# MicroController_Module_Output_Ports.net
KiCad netlist of a schematic drawn in Altium Designer
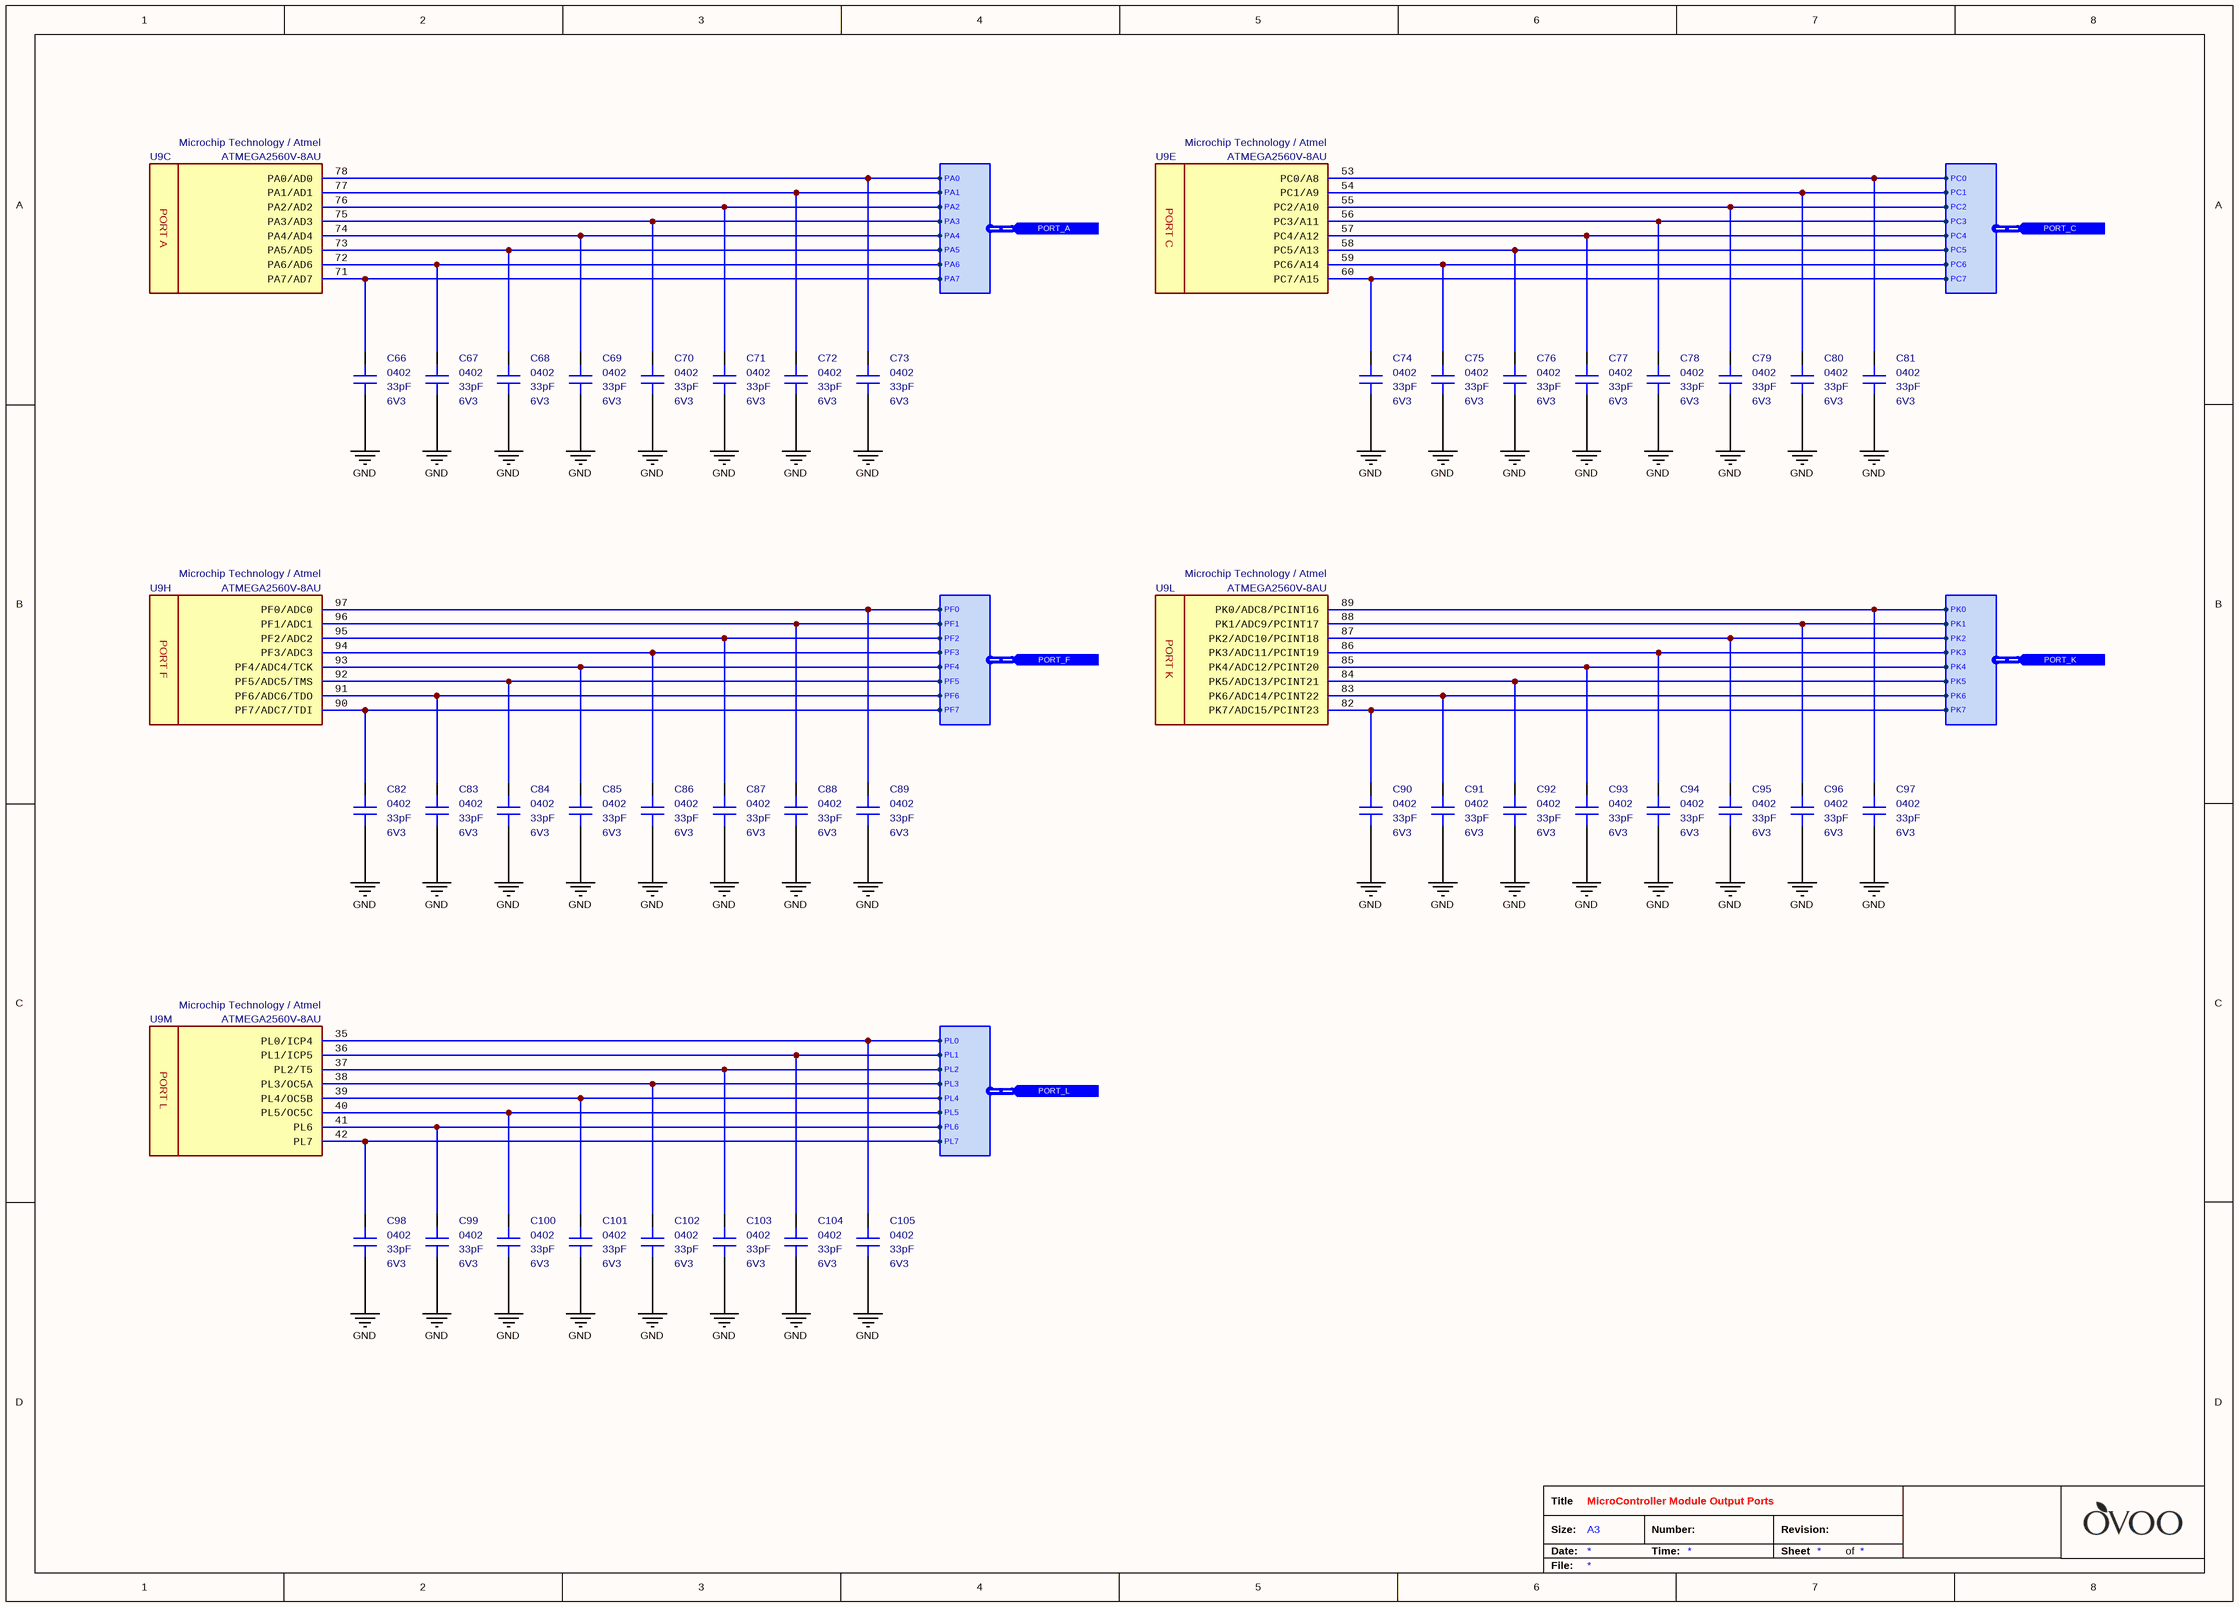
[diagram p0: MicroController Module Output Ports.SchDoc]

(export (version "E")
  (design (tool "Eeschema 10.0.6"))
  (components
    (comp (ref "C66")
      (value "33pF")
      (footprint "CAPACITOR_0402")
      (description "Capacitor - 33pF [0402] (Ceramic)")
      (fields
        (field (name "MANUFACTURER_PART_NUMBER") "C0402C330J9RACAUTO")
        (field (name "MOUSER_PART_NUMBER") "80-C0402C330J9RAUTO")
        (field (name "CASE") "0402")
        (field (name "VOLTAGE") "6V3")
      )
      (libsource (lib "Ovoo_Schematic") (part "Capacitor - 33pF [0402-6V3]"))
    )
    (comp (ref "C67")
      (value "33pF")
      (footprint "CAPACITOR_0402")
      (description "Capacitor - 33pF [0402] (Ceramic)")
      (fields
        (field (name "MANUFACTURER_PART_NUMBER") "C0402C330J9RACAUTO")
        (field (name "MOUSER_PART_NUMBER") "80-C0402C330J9RAUTO")
        (field (name "CASE") "0402")
        (field (name "VOLTAGE") "6V3")
      )
      (libsource (lib "Ovoo_Schematic") (part "Capacitor - 33pF [0402-6V3]"))
    )
    (comp (ref "C68")
      (value "33pF")
      (footprint "CAPACITOR_0402")
      (description "Capacitor - 33pF [0402] (Ceramic)")
      (fields
        (field (name "MANUFACTURER_PART_NUMBER") "C0402C330J9RACAUTO")
        (field (name "MOUSER_PART_NUMBER") "80-C0402C330J9RAUTO")
        (field (name "CASE") "0402")
        (field (name "VOLTAGE") "6V3")
      )
      (libsource (lib "Ovoo_Schematic") (part "Capacitor - 33pF [0402-6V3]"))
    )
    (comp (ref "C69")
      (value "33pF")
      (footprint "CAPACITOR_0402")
      (description "Capacitor - 33pF [0402] (Ceramic)")
      (fields
        (field (name "MANUFACTURER_PART_NUMBER") "C0402C330J9RACAUTO")
        (field (name "MOUSER_PART_NUMBER") "80-C0402C330J9RAUTO")
        (field (name "CASE") "0402")
        (field (name "VOLTAGE") "6V3")
      )
      (libsource (lib "Ovoo_Schematic") (part "Capacitor - 33pF [0402-6V3]"))
    )
    (comp (ref "C70")
      (value "33pF")
      (footprint "CAPACITOR_0402")
      (description "Capacitor - 33pF [0402] (Ceramic)")
      (fields
        (field (name "MANUFACTURER_PART_NUMBER") "C0402C330J9RACAUTO")
        (field (name "MOUSER_PART_NUMBER") "80-C0402C330J9RAUTO")
        (field (name "CASE") "0402")
        (field (name "VOLTAGE") "6V3")
      )
      (libsource (lib "Ovoo_Schematic") (part "Capacitor - 33pF [0402-6V3]"))
    )
    (comp (ref "C71")
      (value "33pF")
      (footprint "CAPACITOR_0402")
      (description "Capacitor - 33pF [0402] (Ceramic)")
      (fields
        (field (name "MANUFACTURER_PART_NUMBER") "C0402C330J9RACAUTO")
        (field (name "MOUSER_PART_NUMBER") "80-C0402C330J9RAUTO")
        (field (name "CASE") "0402")
        (field (name "VOLTAGE") "6V3")
      )
      (libsource (lib "Ovoo_Schematic") (part "Capacitor - 33pF [0402-6V3]"))
    )
    (comp (ref "C72")
      (value "33pF")
      (footprint "CAPACITOR_0402")
      (description "Capacitor - 33pF [0402] (Ceramic)")
      (fields
        (field (name "MANUFACTURER_PART_NUMBER") "C0402C330J9RACAUTO")
        (field (name "MOUSER_PART_NUMBER") "80-C0402C330J9RAUTO")
        (field (name "CASE") "0402")
        (field (name "VOLTAGE") "6V3")
      )
      (libsource (lib "Ovoo_Schematic") (part "Capacitor - 33pF [0402-6V3]"))
    )
    (comp (ref "C73")
      (value "33pF")
      (footprint "CAPACITOR_0402")
      (description "Capacitor - 33pF [0402] (Ceramic)")
      (fields
        (field (name "MANUFACTURER_PART_NUMBER") "C0402C330J9RACAUTO")
        (field (name "MOUSER_PART_NUMBER") "80-C0402C330J9RAUTO")
        (field (name "CASE") "0402")
        (field (name "VOLTAGE") "6V3")
      )
      (libsource (lib "Ovoo_Schematic") (part "Capacitor - 33pF [0402-6V3]"))
    )
    (comp (ref "C74")
      (value "33pF")
      (footprint "CAPACITOR_0402")
      (description "Capacitor - 33pF [0402] (Ceramic)")
      (fields
        (field (name "MANUFACTURER_PART_NUMBER") "C0402C330J9RACAUTO")
        (field (name "MOUSER_PART_NUMBER") "80-C0402C330J9RAUTO")
        (field (name "CASE") "0402")
        (field (name "VOLTAGE") "6V3")
      )
      (libsource (lib "Ovoo_Schematic") (part "Capacitor - 33pF [0402-6V3]"))
    )
    (comp (ref "C75")
      (value "33pF")
      (footprint "CAPACITOR_0402")
      (description "Capacitor - 33pF [0402] (Ceramic)")
      (fields
        (field (name "MANUFACTURER_PART_NUMBER") "C0402C330J9RACAUTO")
        (field (name "MOUSER_PART_NUMBER") "80-C0402C330J9RAUTO")
        (field (name "CASE") "0402")
        (field (name "VOLTAGE") "6V3")
      )
      (libsource (lib "Ovoo_Schematic") (part "Capacitor - 33pF [0402-6V3]"))
    )
    (comp (ref "C76")
      (value "33pF")
      (footprint "CAPACITOR_0402")
      (description "Capacitor - 33pF [0402] (Ceramic)")
      (fields
        (field (name "MANUFACTURER_PART_NUMBER") "C0402C330J9RACAUTO")
        (field (name "MOUSER_PART_NUMBER") "80-C0402C330J9RAUTO")
        (field (name "CASE") "0402")
        (field (name "VOLTAGE") "6V3")
      )
      (libsource (lib "Ovoo_Schematic") (part "Capacitor - 33pF [0402-6V3]"))
    )
    (comp (ref "C77")
      (value "33pF")
      (footprint "CAPACITOR_0402")
      (description "Capacitor - 33pF [0402] (Ceramic)")
      (fields
        (field (name "MANUFACTURER_PART_NUMBER") "C0402C330J9RACAUTO")
        (field (name "MOUSER_PART_NUMBER") "80-C0402C330J9RAUTO")
        (field (name "CASE") "0402")
        (field (name "VOLTAGE") "6V3")
      )
      (libsource (lib "Ovoo_Schematic") (part "Capacitor - 33pF [0402-6V3]"))
    )
    (comp (ref "C78")
      (value "33pF")
      (footprint "CAPACITOR_0402")
      (description "Capacitor - 33pF [0402] (Ceramic)")
      (fields
        (field (name "MANUFACTURER_PART_NUMBER") "C0402C330J9RACAUTO")
        (field (name "MOUSER_PART_NUMBER") "80-C0402C330J9RAUTO")
        (field (name "CASE") "0402")
        (field (name "VOLTAGE") "6V3")
      )
      (libsource (lib "Ovoo_Schematic") (part "Capacitor - 33pF [0402-6V3]"))
    )
    (comp (ref "C79")
      (value "33pF")
      (footprint "CAPACITOR_0402")
      (description "Capacitor - 33pF [0402] (Ceramic)")
      (fields
        (field (name "MANUFACTURER_PART_NUMBER") "C0402C330J9RACAUTO")
        (field (name "MOUSER_PART_NUMBER") "80-C0402C330J9RAUTO")
        (field (name "CASE") "0402")
        (field (name "VOLTAGE") "6V3")
      )
      (libsource (lib "Ovoo_Schematic") (part "Capacitor - 33pF [0402-6V3]"))
    )
    (comp (ref "C80")
      (value "33pF")
      (footprint "CAPACITOR_0402")
      (description "Capacitor - 33pF [0402] (Ceramic)")
      (fields
        (field (name "MANUFACTURER_PART_NUMBER") "C0402C330J9RACAUTO")
        (field (name "MOUSER_PART_NUMBER") "80-C0402C330J9RAUTO")
        (field (name "CASE") "0402")
        (field (name "VOLTAGE") "6V3")
      )
      (libsource (lib "Ovoo_Schematic") (part "Capacitor - 33pF [0402-6V3]"))
    )
    (comp (ref "C81")
      (value "33pF")
      (footprint "CAPACITOR_0402")
      (description "Capacitor - 33pF [0402] (Ceramic)")
      (fields
        (field (name "MANUFACTURER_PART_NUMBER") "C0402C330J9RACAUTO")
        (field (name "MOUSER_PART_NUMBER") "80-C0402C330J9RAUTO")
        (field (name "CASE") "0402")
        (field (name "VOLTAGE") "6V3")
      )
      (libsource (lib "Ovoo_Schematic") (part "Capacitor - 33pF [0402-6V3]"))
    )
    (comp (ref "C82")
      (value "33pF")
      (footprint "CAPACITOR_0402")
      (description "Capacitor - 33pF [0402] (Ceramic)")
      (fields
        (field (name "MANUFACTURER_PART_NUMBER") "C0402C330J9RACAUTO")
        (field (name "MOUSER_PART_NUMBER") "80-C0402C330J9RAUTO")
        (field (name "CASE") "0402")
        (field (name "VOLTAGE") "6V3")
      )
      (libsource (lib "Ovoo_Schematic") (part "Capacitor - 33pF [0402-6V3]"))
    )
    (comp (ref "C83")
      (value "33pF")
      (footprint "CAPACITOR_0402")
      (description "Capacitor - 33pF [0402] (Ceramic)")
      (fields
        (field (name "MANUFACTURER_PART_NUMBER") "C0402C330J9RACAUTO")
        (field (name "MOUSER_PART_NUMBER") "80-C0402C330J9RAUTO")
        (field (name "CASE") "0402")
        (field (name "VOLTAGE") "6V3")
      )
      (libsource (lib "Ovoo_Schematic") (part "Capacitor - 33pF [0402-6V3]"))
    )
    (comp (ref "C84")
      (value "33pF")
      (footprint "CAPACITOR_0402")
      (description "Capacitor - 33pF [0402] (Ceramic)")
      (fields
        (field (name "MANUFACTURER_PART_NUMBER") "C0402C330J9RACAUTO")
        (field (name "MOUSER_PART_NUMBER") "80-C0402C330J9RAUTO")
        (field (name "CASE") "0402")
        (field (name "VOLTAGE") "6V3")
      )
      (libsource (lib "Ovoo_Schematic") (part "Capacitor - 33pF [0402-6V3]"))
    )
    (comp (ref "C85")
      (value "33pF")
      (footprint "CAPACITOR_0402")
      (description "Capacitor - 33pF [0402] (Ceramic)")
      (fields
        (field (name "MANUFACTURER_PART_NUMBER") "C0402C330J9RACAUTO")
        (field (name "MOUSER_PART_NUMBER") "80-C0402C330J9RAUTO")
        (field (name "CASE") "0402")
        (field (name "VOLTAGE") "6V3")
      )
      (libsource (lib "Ovoo_Schematic") (part "Capacitor - 33pF [0402-6V3]"))
    )
    (comp (ref "C86")
      (value "33pF")
      (footprint "CAPACITOR_0402")
      (description "Capacitor - 33pF [0402] (Ceramic)")
      (fields
        (field (name "MANUFACTURER_PART_NUMBER") "C0402C330J9RACAUTO")
        (field (name "MOUSER_PART_NUMBER") "80-C0402C330J9RAUTO")
        (field (name "CASE") "0402")
        (field (name "VOLTAGE") "6V3")
      )
      (libsource (lib "Ovoo_Schematic") (part "Capacitor - 33pF [0402-6V3]"))
    )
    (comp (ref "C87")
      (value "33pF")
      (footprint "CAPACITOR_0402")
      (description "Capacitor - 33pF [0402] (Ceramic)")
      (fields
        (field (name "MANUFACTURER_PART_NUMBER") "C0402C330J9RACAUTO")
        (field (name "MOUSER_PART_NUMBER") "80-C0402C330J9RAUTO")
        (field (name "CASE") "0402")
        (field (name "VOLTAGE") "6V3")
      )
      (libsource (lib "Ovoo_Schematic") (part "Capacitor - 33pF [0402-6V3]"))
    )
    (comp (ref "C88")
      (value "33pF")
      (footprint "CAPACITOR_0402")
      (description "Capacitor - 33pF [0402] (Ceramic)")
      (fields
        (field (name "MANUFACTURER_PART_NUMBER") "C0402C330J9RACAUTO")
        (field (name "MOUSER_PART_NUMBER") "80-C0402C330J9RAUTO")
        (field (name "CASE") "0402")
        (field (name "VOLTAGE") "6V3")
      )
      (libsource (lib "Ovoo_Schematic") (part "Capacitor - 33pF [0402-6V3]"))
    )
    (comp (ref "C89")
      (value "33pF")
      (footprint "CAPACITOR_0402")
      (description "Capacitor - 33pF [0402] (Ceramic)")
      (fields
        (field (name "MANUFACTURER_PART_NUMBER") "C0402C330J9RACAUTO")
        (field (name "MOUSER_PART_NUMBER") "80-C0402C330J9RAUTO")
        (field (name "CASE") "0402")
        (field (name "VOLTAGE") "6V3")
      )
      (libsource (lib "Ovoo_Schematic") (part "Capacitor - 33pF [0402-6V3]"))
    )
    (comp (ref "C90")
      (value "33pF")
      (footprint "CAPACITOR_0402")
      (description "Capacitor - 33pF [0402] (Ceramic)")
      (fields
        (field (name "MANUFACTURER_PART_NUMBER") "C0402C330J9RACAUTO")
        (field (name "MOUSER_PART_NUMBER") "80-C0402C330J9RAUTO")
        (field (name "CASE") "0402")
        (field (name "VOLTAGE") "6V3")
      )
      (libsource (lib "Ovoo_Schematic") (part "Capacitor - 33pF [0402-6V3]"))
    )
    (comp (ref "C91")
      (value "33pF")
      (footprint "CAPACITOR_0402")
      (description "Capacitor - 33pF [0402] (Ceramic)")
      (fields
        (field (name "MANUFACTURER_PART_NUMBER") "C0402C330J9RACAUTO")
        (field (name "MOUSER_PART_NUMBER") "80-C0402C330J9RAUTO")
        (field (name "CASE") "0402")
        (field (name "VOLTAGE") "6V3")
      )
      (libsource (lib "Ovoo_Schematic") (part "Capacitor - 33pF [0402-6V3]"))
    )
    (comp (ref "C92")
      (value "33pF")
      (footprint "CAPACITOR_0402")
      (description "Capacitor - 33pF [0402] (Ceramic)")
      (fields
        (field (name "MANUFACTURER_PART_NUMBER") "C0402C330J9RACAUTO")
        (field (name "MOUSER_PART_NUMBER") "80-C0402C330J9RAUTO")
        (field (name "CASE") "0402")
        (field (name "VOLTAGE") "6V3")
      )
      (libsource (lib "Ovoo_Schematic") (part "Capacitor - 33pF [0402-6V3]"))
    )
    (comp (ref "C93")
      (value "33pF")
      (footprint "CAPACITOR_0402")
      (description "Capacitor - 33pF [0402] (Ceramic)")
      (fields
        (field (name "MANUFACTURER_PART_NUMBER") "C0402C330J9RACAUTO")
        (field (name "MOUSER_PART_NUMBER") "80-C0402C330J9RAUTO")
        (field (name "CASE") "0402")
        (field (name "VOLTAGE") "6V3")
      )
      (libsource (lib "Ovoo_Schematic") (part "Capacitor - 33pF [0402-6V3]"))
    )
    (comp (ref "C94")
      (value "33pF")
      (footprint "CAPACITOR_0402")
      (description "Capacitor - 33pF [0402] (Ceramic)")
      (fields
        (field (name "MANUFACTURER_PART_NUMBER") "C0402C330J9RACAUTO")
        (field (name "MOUSER_PART_NUMBER") "80-C0402C330J9RAUTO")
        (field (name "CASE") "0402")
        (field (name "VOLTAGE") "6V3")
      )
      (libsource (lib "Ovoo_Schematic") (part "Capacitor - 33pF [0402-6V3]"))
    )
    (comp (ref "C95")
      (value "33pF")
      (footprint "CAPACITOR_0402")
      (description "Capacitor - 33pF [0402] (Ceramic)")
      (fields
        (field (name "MANUFACTURER_PART_NUMBER") "C0402C330J9RACAUTO")
        (field (name "MOUSER_PART_NUMBER") "80-C0402C330J9RAUTO")
        (field (name "CASE") "0402")
        (field (name "VOLTAGE") "6V3")
      )
      (libsource (lib "Ovoo_Schematic") (part "Capacitor - 33pF [0402-6V3]"))
    )
    (comp (ref "C96")
      (value "33pF")
      (footprint "CAPACITOR_0402")
      (description "Capacitor - 33pF [0402] (Ceramic)")
      (fields
        (field (name "MANUFACTURER_PART_NUMBER") "C0402C330J9RACAUTO")
        (field (name "MOUSER_PART_NUMBER") "80-C0402C330J9RAUTO")
        (field (name "CASE") "0402")
        (field (name "VOLTAGE") "6V3")
      )
      (libsource (lib "Ovoo_Schematic") (part "Capacitor - 33pF [0402-6V3]"))
    )
    (comp (ref "C97")
      (value "33pF")
      (footprint "CAPACITOR_0402")
      (description "Capacitor - 33pF [0402] (Ceramic)")
      (fields
        (field (name "MANUFACTURER_PART_NUMBER") "C0402C330J9RACAUTO")
        (field (name "MOUSER_PART_NUMBER") "80-C0402C330J9RAUTO")
        (field (name "CASE") "0402")
        (field (name "VOLTAGE") "6V3")
      )
      (libsource (lib "Ovoo_Schematic") (part "Capacitor - 33pF [0402-6V3]"))
    )
    (comp (ref "C98")
      (value "33pF")
      (footprint "CAPACITOR_0402")
      (description "Capacitor - 33pF [0402] (Ceramic)")
      (fields
        (field (name "MANUFACTURER_PART_NUMBER") "C0402C330J9RACAUTO")
        (field (name "MOUSER_PART_NUMBER") "80-C0402C330J9RAUTO")
        (field (name "CASE") "0402")
        (field (name "VOLTAGE") "6V3")
      )
      (libsource (lib "Ovoo_Schematic") (part "Capacitor - 33pF [0402-6V3]"))
    )
    (comp (ref "C99")
      (value "33pF")
      (footprint "CAPACITOR_0402")
      (description "Capacitor - 33pF [0402] (Ceramic)")
      (fields
        (field (name "MANUFACTURER_PART_NUMBER") "C0402C330J9RACAUTO")
        (field (name "MOUSER_PART_NUMBER") "80-C0402C330J9RAUTO")
        (field (name "CASE") "0402")
        (field (name "VOLTAGE") "6V3")
      )
      (libsource (lib "Ovoo_Schematic") (part "Capacitor - 33pF [0402-6V3]"))
    )
    (comp (ref "C100")
      (value "33pF")
      (footprint "CAPACITOR_0402")
      (description "Capacitor - 33pF [0402] (Ceramic)")
      (fields
        (field (name "MANUFACTURER_PART_NUMBER") "C0402C330J9RACAUTO")
        (field (name "MOUSER_PART_NUMBER") "80-C0402C330J9RAUTO")
        (field (name "CASE") "0402")
        (field (name "VOLTAGE") "6V3")
      )
      (libsource (lib "Ovoo_Schematic") (part "Capacitor - 33pF [0402-6V3]"))
    )
    (comp (ref "C101")
      (value "33pF")
      (footprint "CAPACITOR_0402")
      (description "Capacitor - 33pF [0402] (Ceramic)")
      (fields
        (field (name "MANUFACTURER_PART_NUMBER") "C0402C330J9RACAUTO")
        (field (name "MOUSER_PART_NUMBER") "80-C0402C330J9RAUTO")
        (field (name "CASE") "0402")
        (field (name "VOLTAGE") "6V3")
      )
      (libsource (lib "Ovoo_Schematic") (part "Capacitor - 33pF [0402-6V3]"))
    )
    (comp (ref "C102")
      (value "33pF")
      (footprint "CAPACITOR_0402")
      (description "Capacitor - 33pF [0402] (Ceramic)")
      (fields
        (field (name "MANUFACTURER_PART_NUMBER") "C0402C330J9RACAUTO")
        (field (name "MOUSER_PART_NUMBER") "80-C0402C330J9RAUTO")
        (field (name "CASE") "0402")
        (field (name "VOLTAGE") "6V3")
      )
      (libsource (lib "Ovoo_Schematic") (part "Capacitor - 33pF [0402-6V3]"))
    )
    (comp (ref "C103")
      (value "33pF")
      (footprint "CAPACITOR_0402")
      (description "Capacitor - 33pF [0402] (Ceramic)")
      (fields
        (field (name "MANUFACTURER_PART_NUMBER") "C0402C330J9RACAUTO")
        (field (name "MOUSER_PART_NUMBER") "80-C0402C330J9RAUTO")
        (field (name "CASE") "0402")
        (field (name "VOLTAGE") "6V3")
      )
      (libsource (lib "Ovoo_Schematic") (part "Capacitor - 33pF [0402-6V3]"))
    )
    (comp (ref "C104")
      (value "33pF")
      (footprint "CAPACITOR_0402")
      (description "Capacitor - 33pF [0402] (Ceramic)")
      (fields
        (field (name "MANUFACTURER_PART_NUMBER") "C0402C330J9RACAUTO")
        (field (name "MOUSER_PART_NUMBER") "80-C0402C330J9RAUTO")
        (field (name "CASE") "0402")
        (field (name "VOLTAGE") "6V3")
      )
      (libsource (lib "Ovoo_Schematic") (part "Capacitor - 33pF [0402-6V3]"))
    )
    (comp (ref "C105")
      (value "33pF")
      (footprint "CAPACITOR_0402")
      (description "Capacitor - 33pF [0402] (Ceramic)")
      (fields
        (field (name "MANUFACTURER_PART_NUMBER") "C0402C330J9RACAUTO")
        (field (name "MOUSER_PART_NUMBER") "80-C0402C330J9RAUTO")
        (field (name "CASE") "0402")
        (field (name "VOLTAGE") "6V3")
      )
      (libsource (lib "Ovoo_Schematic") (part "Capacitor - 33pF [0402-6V3]"))
    )
    (comp (ref "U9")
      (value "8-bit MicroController")
      (footprint "TQFP100")
      (description "8-bit Microcontrollers - MCU 256kB Flash 4kB EEPROM 86 I/O Pins")
      (fields
        (field (name "MOUSER_PART_NUMBER") "556-ATMEGA2560V8AU")
        (field (name "MANUFACTURER_PART_NUMBER") "ATMEGA2560V-8AU")
        (field (name "MANUFACTURER_NAME") "Microchip Technology / Atmel")
      )
      (libsource (lib "Ovoo_Library") (part "IC - ATMEGA2560V-8AU"))
    )
  )
  (nets
    (net (code "11") (name "GND") (class "Default")
      (node (ref "C100") (pin "1") (pinfunction "1_1") (pintype "passive"))
      (node (ref "C101") (pin "1") (pinfunction "1_1") (pintype "passive"))
      (node (ref "C102") (pin "1") (pinfunction "1_1") (pintype "passive"))
      (node (ref "C103") (pin "1") (pinfunction "1_1") (pintype "passive"))
      (node (ref "C104") (pin "1") (pinfunction "1_1") (pintype "passive"))
      (node (ref "C105") (pin "1") (pinfunction "1_1") (pintype "passive"))
      (node (ref "C66") (pin "1") (pinfunction "1_1") (pintype "passive"))
      (node (ref "C67") (pin "1") (pinfunction "1_1") (pintype "passive"))
      (node (ref "C68") (pin "1") (pinfunction "1_1") (pintype "passive"))
      (node (ref "C69") (pin "1") (pinfunction "1_1") (pintype "passive"))
      (node (ref "C70") (pin "1") (pinfunction "1_1") (pintype "passive"))
      (node (ref "C71") (pin "1") (pinfunction "1_1") (pintype "passive"))
      (node (ref "C72") (pin "1") (pinfunction "1_1") (pintype "passive"))
      (node (ref "C73") (pin "1") (pinfunction "1_1") (pintype "passive"))
      (node (ref "C74") (pin "1") (pinfunction "1_1") (pintype "passive"))
      (node (ref "C75") (pin "1") (pinfunction "1_1") (pintype "passive"))
      (node (ref "C76") (pin "1") (pinfunction "1_1") (pintype "passive"))
      (node (ref "C77") (pin "1") (pinfunction "1_1") (pintype "passive"))
      (node (ref "C78") (pin "1") (pinfunction "1_1") (pintype "passive"))
      (node (ref "C79") (pin "1") (pinfunction "1_1") (pintype "passive"))
      (node (ref "C80") (pin "1") (pinfunction "1_1") (pintype "passive"))
      (node (ref "C81") (pin "1") (pinfunction "1_1") (pintype "passive"))
      (node (ref "C82") (pin "1") (pinfunction "1_1") (pintype "passive"))
      (node (ref "C83") (pin "1") (pinfunction "1_1") (pintype "passive"))
      (node (ref "C84") (pin "1") (pinfunction "1_1") (pintype "passive"))
      (node (ref "C85") (pin "1") (pinfunction "1_1") (pintype "passive"))
      (node (ref "C86") (pin "1") (pinfunction "1_1") (pintype "passive"))
      (node (ref "C87") (pin "1") (pinfunction "1_1") (pintype "passive"))
      (node (ref "C88") (pin "1") (pinfunction "1_1") (pintype "passive"))
      (node (ref "C89") (pin "1") (pinfunction "1_1") (pintype "passive"))
      (node (ref "C90") (pin "1") (pinfunction "1_1") (pintype "passive"))
      (node (ref "C91") (pin "1") (pinfunction "1_1") (pintype "passive"))
      (node (ref "C92") (pin "1") (pinfunction "1_1") (pintype "passive"))
      (node (ref "C93") (pin "1") (pinfunction "1_1") (pintype "passive"))
      (node (ref "C94") (pin "1") (pinfunction "1_1") (pintype "passive"))
      (node (ref "C95") (pin "1") (pinfunction "1_1") (pintype "passive"))
      (node (ref "C96") (pin "1") (pinfunction "1_1") (pintype "passive"))
      (node (ref "C97") (pin "1") (pinfunction "1_1") (pintype "passive"))
      (node (ref "C98") (pin "1") (pinfunction "1_1") (pintype "passive"))
      (node (ref "C99") (pin "1") (pinfunction "1_1") (pintype "passive"))
    )
    (net (code "12") (name "Net-(U9C-PA0{slash}AD0)") (class "Default")
      (node (ref "C73") (pin "2") (pinfunction "2_2") (pintype "passive"))
      (node (ref "U9") (pin "78") (pinfunction "PA0/AD0_78") (pintype "passive"))
    )
    (net (code "13") (name "Net-(U9C-PA1{slash}AD1)") (class "Default")
      (node (ref "C72") (pin "2") (pinfunction "2_2") (pintype "passive"))
      (node (ref "U9") (pin "77") (pinfunction "PA1/AD1_77") (pintype "passive"))
    )
    (net (code "14") (name "Net-(U9C-PA2{slash}AD2)") (class "Default")
      (node (ref "C71") (pin "2") (pinfunction "2_2") (pintype "passive"))
      (node (ref "U9") (pin "76") (pinfunction "PA2/AD2_76") (pintype "passive"))
    )
    (net (code "15") (name "Net-(U9C-PA3{slash}AD3)") (class "Default")
      (node (ref "C70") (pin "2") (pinfunction "2_2") (pintype "passive"))
      (node (ref "U9") (pin "75") (pinfunction "PA3/AD3_75") (pintype "passive"))
    )
    (net (code "16") (name "Net-(U9C-PA4{slash}AD4)") (class "Default")
      (node (ref "C69") (pin "2") (pinfunction "2_2") (pintype "passive"))
      (node (ref "U9") (pin "74") (pinfunction "PA4/AD4_74") (pintype "passive"))
    )
    (net (code "17") (name "Net-(U9C-PA5{slash}AD5)") (class "Default")
      (node (ref "C68") (pin "2") (pinfunction "2_2") (pintype "passive"))
      (node (ref "U9") (pin "73") (pinfunction "PA5/AD5_73") (pintype "passive"))
    )
    (net (code "18") (name "Net-(U9C-PA6{slash}AD6)") (class "Default")
      (node (ref "C67") (pin "2") (pinfunction "2_2") (pintype "passive"))
      (node (ref "U9") (pin "72") (pinfunction "PA6/AD6_72") (pintype "passive"))
    )
    (net (code "19") (name "Net-(U9C-PA7{slash}AD7)") (class "Default")
      (node (ref "C66") (pin "2") (pinfunction "2_2") (pintype "passive"))
      (node (ref "U9") (pin "71") (pinfunction "PA7/AD7_71") (pintype "passive"))
    )
    (net (code "20") (name "Net-(U9E-PC0{slash}A8)") (class "Default")
      (node (ref "C81") (pin "2") (pinfunction "2_2") (pintype "passive"))
      (node (ref "U9") (pin "53") (pinfunction "PC0/A8_53") (pintype "passive"))
    )
    (net (code "21") (name "Net-(U9E-PC1{slash}A9)") (class "Default")
      (node (ref "C80") (pin "2") (pinfunction "2_2") (pintype "passive"))
      (node (ref "U9") (pin "54") (pinfunction "PC1/A9_54") (pintype "passive"))
    )
    (net (code "22") (name "Net-(U9E-PC2{slash}A10)") (class "Default")
      (node (ref "C79") (pin "2") (pinfunction "2_2") (pintype "passive"))
      (node (ref "U9") (pin "55") (pinfunction "PC2/A10_55") (pintype "passive"))
    )
    (net (code "23") (name "Net-(U9E-PC3{slash}A11)") (class "Default")
      (node (ref "C78") (pin "2") (pinfunction "2_2") (pintype "passive"))
      (node (ref "U9") (pin "56") (pinfunction "PC3/A11_56") (pintype "passive"))
    )
    (net (code "24") (name "Net-(U9E-PC4{slash}A12)") (class "Default")
      (node (ref "C77") (pin "2") (pinfunction "2_2") (pintype "passive"))
      (node (ref "U9") (pin "57") (pinfunction "PC4/A12_57") (pintype "passive"))
    )
    (net (code "25") (name "Net-(U9E-PC5{slash}A13)") (class "Default")
      (node (ref "C76") (pin "2") (pinfunction "2_2") (pintype "passive"))
      (node (ref "U9") (pin "58") (pinfunction "PC5/A13_58") (pintype "passive"))
    )
    (net (code "26") (name "Net-(U9E-PC6{slash}A14)") (class "Default")
      (node (ref "C75") (pin "2") (pinfunction "2_2") (pintype "passive"))
      (node (ref "U9") (pin "59") (pinfunction "PC6/A14_59") (pintype "passive"))
    )
    (net (code "27") (name "Net-(U9E-PC7{slash}A15)") (class "Default")
      (node (ref "C74") (pin "2") (pinfunction "2_2") (pintype "passive"))
      (node (ref "U9") (pin "60") (pinfunction "PC7/A15_60") (pintype "passive"))
    )
    (net (code "28") (name "Net-(U9H-PF0{slash}ADC0)") (class "Default")
      (node (ref "C89") (pin "2") (pinfunction "2_2") (pintype "passive"))
      (node (ref "U9") (pin "97") (pinfunction "PF0/ADC0_97") (pintype "passive"))
    )
    (net (code "29") (name "Net-(U9H-PF1{slash}ADC1)") (class "Default")
      (node (ref "C88") (pin "2") (pinfunction "2_2") (pintype "passive"))
      (node (ref "U9") (pin "96") (pinfunction "PF1/ADC1_96") (pintype "passive"))
    )
    (net (code "30") (name "Net-(U9H-PF2{slash}ADC2)") (class "Default")
      (node (ref "C87") (pin "2") (pinfunction "2_2") (pintype "passive"))
      (node (ref "U9") (pin "95") (pinfunction "PF2/ADC2_95") (pintype "passive"))
    )
    (net (code "31") (name "Net-(U9H-PF3{slash}ADC3)") (class "Default")
      (node (ref "C86") (pin "2") (pinfunction "2_2") (pintype "passive"))
      (node (ref "U9") (pin "94") (pinfunction "PF3/ADC3_94") (pintype "passive"))
    )
    (net (code "32") (name "Net-(U9H-PF4{slash}ADC4{slash}TCK)") (class "Default")
      (node (ref "C85") (pin "2") (pinfunction "2_2") (pintype "passive"))
      (node (ref "U9") (pin "93") (pinfunction "PF4/ADC4/TCK_93") (pintype "passive"))
    )
    (net (code "33") (name "Net-(U9H-PF5{slash}ADC5{slash}TMS)") (class "Default")
      (node (ref "C84") (pin "2") (pinfunction "2_2") (pintype "passive"))
      (node (ref "U9") (pin "92") (pinfunction "PF5/ADC5/TMS_92") (pintype "passive"))
    )
    (net (code "34") (name "Net-(U9H-PF6{slash}ADC6{slash}TDO)") (class "Default")
      (node (ref "C83") (pin "2") (pinfunction "2_2") (pintype "passive"))
      (node (ref "U9") (pin "91") (pinfunction "PF6/ADC6/TDO_91") (pintype "passive"))
    )
    (net (code "35") (name "Net-(U9H-PF7{slash}ADC7{slash}TDI)") (class "Default")
      (node (ref "C82") (pin "2") (pinfunction "2_2") (pintype "passive"))
      (node (ref "U9") (pin "90") (pinfunction "PF7/ADC7/TDI_90") (pintype "passive"))
    )
    (net (code "36") (name "Net-(U9L-PK0{slash}ADC8{slash}PCINT16)") (class "Default")
      (node (ref "C97") (pin "2") (pinfunction "2_2") (pintype "passive"))
      (node (ref "U9") (pin "89") (pinfunction "PK0/ADC8/PCINT16_89") (pintype "passive"))
    )
    (net (code "37") (name "Net-(U9L-PK1{slash}ADC9{slash}PCINT17)") (class "Default")
      (node (ref "C96") (pin "2") (pinfunction "2_2") (pintype "passive"))
      (node (ref "U9") (pin "88") (pinfunction "PK1/ADC9/PCINT17_88") (pintype "passive"))
    )
    (net (code "38") (name "Net-(U9L-PK2{slash}ADC10{slash}PCINT18)") (class "Default")
      (node (ref "C95") (pin "2") (pinfunction "2_2") (pintype "passive"))
      (node (ref "U9") (pin "87") (pinfunction "PK2/ADC10/PCINT18_87") (pintype "passive"))
    )
    (net (code "39") (name "Net-(U9L-PK3{slash}ADC11{slash}PCINT19)") (class "Default")
      (node (ref "C94") (pin "2") (pinfunction "2_2") (pintype "passive"))
      (node (ref "U9") (pin "86") (pinfunction "PK3/ADC11/PCINT19_86") (pintype "passive"))
    )
    (net (code "40") (name "Net-(U9L-PK4{slash}ADC12{slash}PCINT20)") (class "Default")
      (node (ref "C93") (pin "2") (pinfunction "2_2") (pintype "passive"))
      (node (ref "U9") (pin "85") (pinfunction "PK4/ADC12/PCINT20_85") (pintype "passive"))
    )
    (net (code "41") (name "Net-(U9L-PK5{slash}ADC13{slash}PCINT21)") (class "Default")
      (node (ref "C92") (pin "2") (pinfunction "2_2") (pintype "passive"))
      (node (ref "U9") (pin "84") (pinfunction "PK5/ADC13/PCINT21_84") (pintype "passive"))
    )
    (net (code "42") (name "Net-(U9L-PK6{slash}ADC14{slash}PCINT22)") (class "Default")
      (node (ref "C91") (pin "2") (pinfunction "2_2") (pintype "passive"))
      (node (ref "U9") (pin "83") (pinfunction "PK6/ADC14/PCINT22_83") (pintype "passive"))
    )
    (net (code "43") (name "Net-(U9L-PK7{slash}ADC15{slash}PCINT23)") (class "Default")
      (node (ref "C90") (pin "2") (pinfunction "2_2") (pintype "passive"))
      (node (ref "U9") (pin "82") (pinfunction "PK7/ADC15/PCINT23_82") (pintype "passive"))
    )
    (net (code "44") (name "Net-(U9M-PL0{slash}ICP4)") (class "Default")
      (node (ref "C105") (pin "2") (pinfunction "2_2") (pintype "passive"))
      (node (ref "U9") (pin "35") (pinfunction "PL0/ICP4_35") (pintype "passive"))
    )
    (net (code "45") (name "Net-(U9M-PL1{slash}ICP5)") (class "Default")
      (node (ref "C104") (pin "2") (pinfunction "2_2") (pintype "passive"))
      (node (ref "U9") (pin "36") (pinfunction "PL1/ICP5_36") (pintype "passive"))
    )
    (net (code "46") (name "Net-(U9M-PL2{slash}T5)") (class "Default")
      (node (ref "C103") (pin "2") (pinfunction "2_2") (pintype "passive"))
      (node (ref "U9") (pin "37") (pinfunction "PL2/T5_37") (pintype "passive"))
    )
    (net (code "47") (name "Net-(U9M-PL3{slash}OC5A)") (class "Default")
      (node (ref "C102") (pin "2") (pinfunction "2_2") (pintype "passive"))
      (node (ref "U9") (pin "38") (pinfunction "PL3/OC5A_38") (pintype "passive"))
    )
    (net (code "48") (name "Net-(U9M-PL4{slash}OC5B)") (class "Default")
      (node (ref "C101") (pin "2") (pinfunction "2_2") (pintype "passive"))
      (node (ref "U9") (pin "39") (pinfunction "PL4/OC5B_39") (pintype "passive"))
    )
    (net (code "49") (name "Net-(U9M-PL5{slash}OC5C)") (class "Default")
      (node (ref "C100") (pin "2") (pinfunction "2_2") (pintype "passive"))
      (node (ref "U9") (pin "40") (pinfunction "PL5/OC5C_40") (pintype "passive"))
    )
    (net (code "50") (name "Net-(U9M-PL6)") (class "Default")
      (node (ref "C99") (pin "2") (pinfunction "2_2") (pintype "passive"))
      (node (ref "U9") (pin "41") (pinfunction "PL6_41") (pintype "passive"))
    )
    (net (code "51") (name "Net-(U9M-PL7)") (class "Default")
      (node (ref "C98") (pin "2") (pinfunction "2_2") (pintype "passive"))
      (node (ref "U9") (pin "42") (pinfunction "PL7_42") (pintype "passive"))
    )
  )
)
